# SINTETIZADOR_Y_DDS_SLAVE.net
KiCad netlist of a schematic drawn in Altium Designer
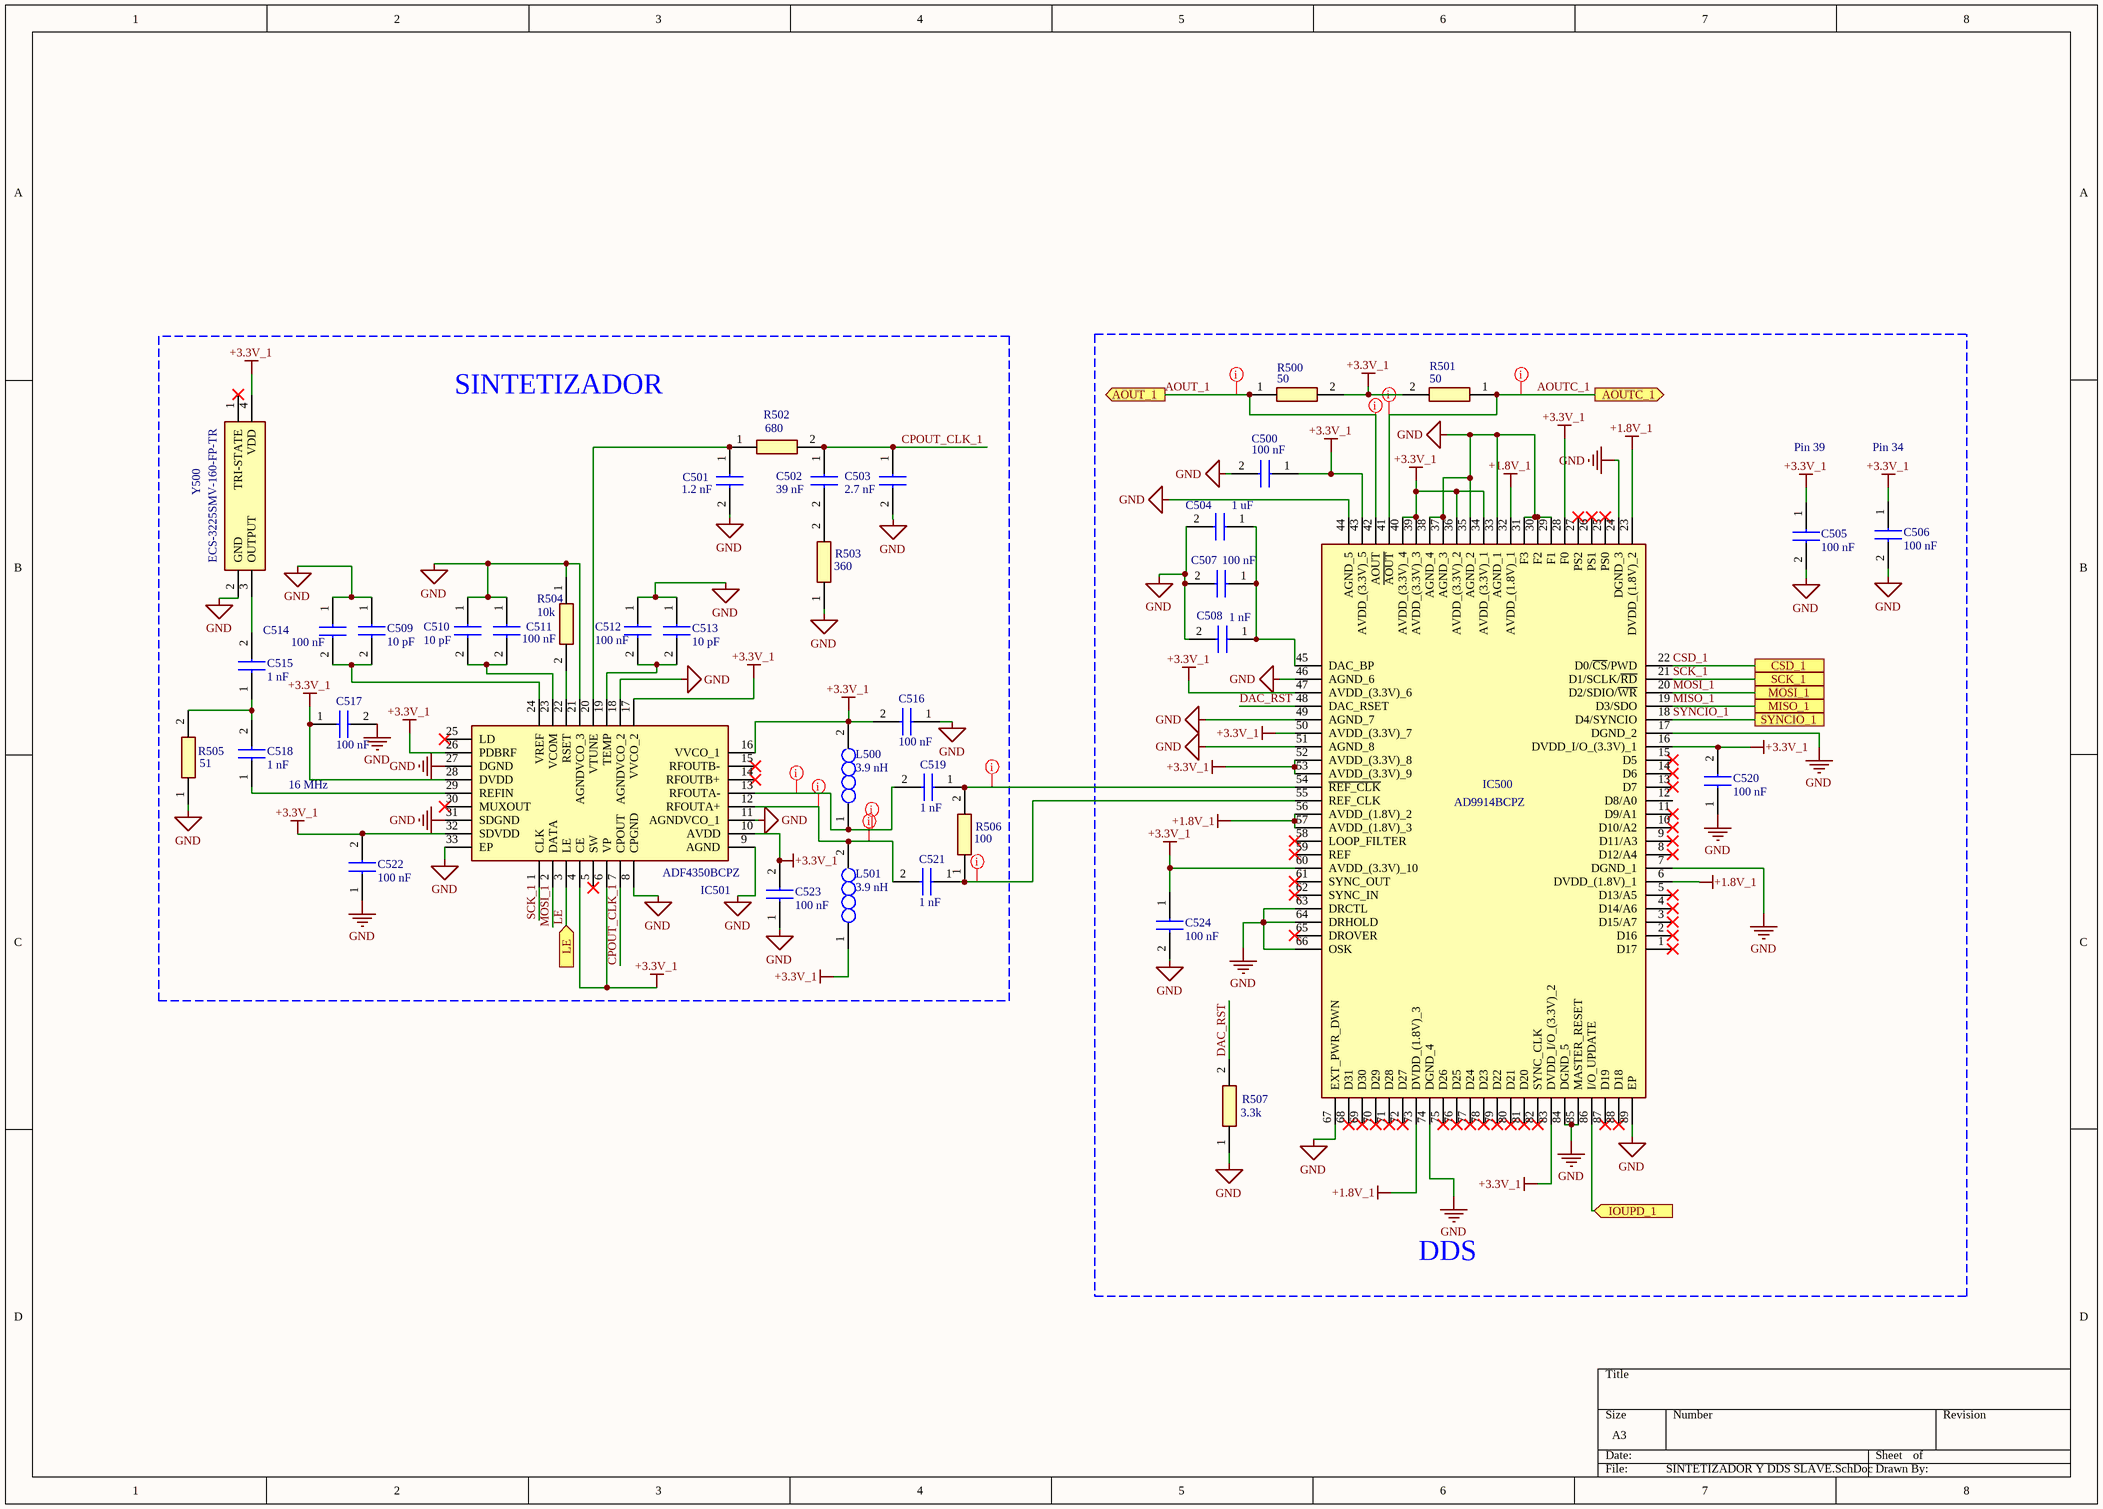
[diagram p0: SINTETIZADOR Y DDS SLAVE.SchDoc]

(export (version "E")
  (design (tool "Eeschema 10.0.6"))
  (components
    (comp (ref "C500")
      (value "100 nF")
      (footprint "SamacSys:C0603")
      (description "Capacitor")
      (fields (field (name "MANUFACTURER_PART_NUMBER") "C0603H470J5GACTU"))
      (libsource (lib "LIBRERIA_GEN_V2.0") (part "C0603H470J5GACTU"))
    )
    (comp (ref "C501")
      (value "1.2 nF")
      (footprint "SamacSys:C0603")
      (description "Capacitor")
      (fields (field (name "MANUFACTURER_PART_NUMBER") "C0603H470J5GACTU"))
      (libsource (lib "LIBRERIA_GEN_V2.0") (part "C0603H470J5GACTU"))
    )
    (comp (ref "C502")
      (value "39 nF")
      (footprint "SamacSys:C0603")
      (description "Capacitor")
      (fields (field (name "MANUFACTURER_PART_NUMBER") "C0603H470J5GACTU"))
      (libsource (lib "LIBRERIA_GEN_V2.0") (part "C0603H470J5GACTU"))
    )
    (comp (ref "C503")
      (value "2.7 nF")
      (footprint "SamacSys:C0603")
      (description "Capacitor")
      (fields (field (name "MANUFACTURER_PART_NUMBER") "C0603H470J5GACTU"))
      (libsource (lib "LIBRERIA_GEN_V2.0") (part "C0603H470J5GACTU"))
    )
    (comp (ref "C504")
      (value "1 uF")
      (footprint "SamacSys:C0603")
      (description "Capacitor")
      (fields (field (name "MANUFACTURER_PART_NUMBER") "C0603H470J5GACTU"))
      (libsource (lib "LIBRERIA_GEN_V2.0") (part "C0603H470J5GACTU"))
    )
    (comp (ref "C505")
      (value "100 nF")
      (footprint "SamacSys:C0603")
      (description "Capacitor")
      (fields (field (name "MANUFACTURER_PART_NUMBER") "C0603H470J5GACTU"))
      (libsource (lib "LIBRERIA_GEN_V2.0") (part "C0603H470J5GACTU"))
    )
    (comp (ref "C506")
      (value "100 nF")
      (footprint "SamacSys:C0603")
      (description "Capacitor")
      (fields (field (name "MANUFACTURER_PART_NUMBER") "C0603H470J5GACTU"))
      (libsource (lib "LIBRERIA_GEN_V2.0") (part "C0603H470J5GACTU"))
    )
    (comp (ref "C507")
      (value "100 nF")
      (footprint "SamacSys:C0603")
      (description "Capacitor")
      (fields (field (name "MANUFACTURER_PART_NUMBER") "C0603H470J5GACTU"))
      (libsource (lib "LIBRERIA_GEN_V2.0") (part "C0603H470J5GACTU"))
    )
    (comp (ref "C508")
      (value "1 nF")
      (footprint "SamacSys:C0603")
      (description "Capacitor")
      (fields (field (name "MANUFACTURER_PART_NUMBER") "C0603H470J5GACTU"))
      (libsource (lib "LIBRERIA_GEN_V2.0") (part "C0603H470J5GACTU"))
    )
    (comp (ref "C509")
      (value "10 pF")
      (footprint "SamacSys:C0603")
      (description "Capacitor")
      (fields (field (name "MANUFACTURER_PART_NUMBER") "C0603H470J5GACTU"))
      (libsource (lib "LIBRERIA_GEN_V2.0") (part "C0603H470J5GACTU"))
    )
    (comp (ref "C510")
      (value "10 pF")
      (footprint "SamacSys:C0603")
      (description "Capacitor")
      (fields (field (name "MANUFACTURER_PART_NUMBER") "C0603H470J5GACTU"))
      (libsource (lib "LIBRERIA_GEN_V2.0") (part "C0603H470J5GACTU"))
    )
    (comp (ref "C511")
      (value "100 nF")
      (footprint "SamacSys:C0603")
      (description "Capacitor")
      (fields (field (name "MANUFACTURER_PART_NUMBER") "C0603H470J5GACTU"))
      (libsource (lib "LIBRERIA_GEN_V2.0") (part "C0603H470J5GACTU"))
    )
    (comp (ref "C512")
      (value "100 nF")
      (footprint "SamacSys:C0603")
      (description "Capacitor")
      (fields (field (name "MANUFACTURER_PART_NUMBER") "C0603H470J5GACTU"))
      (libsource (lib "LIBRERIA_GEN_V2.0") (part "C0603H470J5GACTU"))
    )
    (comp (ref "C513")
      (value "10 pF")
      (footprint "SamacSys:C0603")
      (description "Capacitor")
      (fields (field (name "MANUFACTURER_PART_NUMBER") "C0603H470J5GACTU"))
      (libsource (lib "LIBRERIA_GEN_V2.0") (part "C0603H470J5GACTU"))
    )
    (comp (ref "C514")
      (value "100 nF")
      (footprint "SamacSys:C0603")
      (description "Capacitor")
      (fields (field (name "MANUFACTURER_PART_NUMBER") "C0603H470J5GACTU"))
      (libsource (lib "LIBRERIA_GEN_V2.0") (part "C0603H470J5GACTU"))
    )
    (comp (ref "C515")
      (value "1 nF")
      (footprint "SamacSys:C0603")
      (description "Capacitor")
      (fields (field (name "MANUFACTURER_PART_NUMBER") "C0603H470J5GACTU"))
      (libsource (lib "LIBRERIA_GEN_V2.0") (part "C0603H470J5GACTU"))
    )
    (comp (ref "C516")
      (value "100 nF")
      (footprint "SamacSys:C0603")
      (description "Capacitor")
      (fields (field (name "MANUFACTURER_PART_NUMBER") "C0603H470J5GACTU"))
      (libsource (lib "LIBRERIA_GEN_V2.0") (part "C0603H470J5GACTU"))
    )
    (comp (ref "C517")
      (value "100 nF")
      (footprint "SamacSys:C0603")
      (description "Capacitor")
      (fields (field (name "MANUFACTURER_PART_NUMBER") "C0603H470J5GACTU"))
      (libsource (lib "LIBRERIA_GEN_V2.0") (part "C0603H470J5GACTU"))
    )
    (comp (ref "C518")
      (value "1 nF")
      (footprint "SamacSys:C0603")
      (description "Capacitor")
      (fields (field (name "MANUFACTURER_PART_NUMBER") "C0603H470J5GACTU"))
      (libsource (lib "LIBRERIA_GEN_V2.0") (part "C0603H470J5GACTU"))
    )
    (comp (ref "C519")
      (value "1 nF")
      (footprint "SamacSys:C0603")
      (description "Capacitor")
      (fields (field (name "MANUFACTURER_PART_NUMBER") "C0603H470J5GACTU"))
      (libsource (lib "LIBRERIA_GEN_V2.0") (part "C0603H470J5GACTU"))
    )
    (comp (ref "C520")
      (value "100 nF")
      (footprint "SamacSys:C0603")
      (description "Capacitor")
      (fields (field (name "MANUFACTURER_PART_NUMBER") "C0603H470J5GACTU"))
      (libsource (lib "LIBRERIA_GEN_V2.0") (part "C0603H470J5GACTU"))
    )
    (comp (ref "C521")
      (value "1 nF")
      (footprint "SamacSys:C0603")
      (description "Capacitor")
      (fields (field (name "MANUFACTURER_PART_NUMBER") "C0603H470J5GACTU"))
      (libsource (lib "LIBRERIA_GEN_V2.0") (part "C0603H470J5GACTU"))
    )
    (comp (ref "C522")
      (value "100 nF")
      (footprint "SamacSys:C0603")
      (description "Capacitor")
      (fields (field (name "MANUFACTURER_PART_NUMBER") "C0603H470J5GACTU"))
      (libsource (lib "LIBRERIA_GEN_V2.0") (part "C0603H470J5GACTU"))
    )
    (comp (ref "C523")
      (value "100 nF")
      (footprint "SamacSys:C0603")
      (description "Capacitor")
      (fields (field (name "MANUFACTURER_PART_NUMBER") "C0603H470J5GACTU"))
      (libsource (lib "LIBRERIA_GEN_V2.0") (part "C0603H470J5GACTU"))
    )
    (comp (ref "C524")
      (value "100 nF")
      (footprint "SamacSys:C0603")
      (description "Capacitor")
      (fields (field (name "MANUFACTURER_PART_NUMBER") "C0603H470J5GACTU"))
      (libsource (lib "LIBRERIA_GEN_V2.0") (part "C0603H470J5GACTU"))
    )
    (comp (ref "IC500")
      (value "AD9914BCPZ")
      (footprint "SamacSys:QFN50P1200X1200X90-89N-D")
      (description "Integrated Circuit")
      (fields (field (name "MOUSER PART NUMBER") "584-AD9914BCPZ"))
      (libsource (lib "LIBRERIA_GEN_V2.0") (part "AD9914BCPZ"))
    )
    (comp (ref "IC501")
      (value "ADF4350BCPZ")
      (footprint "SamacSys:QFN50P500X500X100-33N")
      (description "Integrated Circuit")
      (fields (field (name "MOUSER PART NUMBER") "584-ADF4350BCPZ"))
      (libsource (lib "LIBRERIA_GEN_V2.0") (part "ADF4350BCPZ"))
    )
    (comp (ref "L500")
      (value "3.9 nH")
      (footprint "SamacSys:INDC1608X95N")
      (description "Inductor")
      (fields
        (field (name "MANUFACTURER_PART_NUMBER") "AIML-0603-100K-T")
        (field (name "MOUSER PART NUMBER") "815-AIML-0603-100KT")
      )
      (libsource (lib "*") (part "AIML-0603-100K-T"))
    )
    (comp (ref "L501")
      (value "3.9 nH")
      (footprint "SamacSys:INDC1608X95N")
      (description "Inductor")
      (fields
        (field (name "MANUFACTURER_PART_NUMBER") "AIML-0603-100K-T")
        (field (name "MOUSER PART NUMBER") "815-AIML-0603-100KT")
      )
      (libsource (lib "*") (part "AIML-0603-100K-T"))
    )
    (comp (ref "R500")
      (value "50")
      (footprint "SamacSys:RESC1608X55N")
      (description "Resistor")
      (fields
        (field (name "MANUFACTURER_PART_NUMBER") "CR0603-FX-1431ELF")
        (field (name "MOUSER PART NUMBER") "652-CR0603FX-1431ELF")
      )
      (libsource (lib "LIBRERIA_GEN_V2.0") (part "CR0603-FX-1431ELF"))
    )
    (comp (ref "R501")
      (value "50")
      (footprint "SamacSys:RESC1608X55N")
      (description "Resistor")
      (fields
        (field (name "MANUFACTURER_PART_NUMBER") "CR0603-FX-1431ELF")
        (field (name "MOUSER PART NUMBER") "652-CR0603FX-1431ELF")
      )
      (libsource (lib "") (part "CR0603-FX-1431ELF_2"))
    )
    (comp (ref "R502")
      (value "680")
      (footprint "SamacSys:RESC1608X55N")
      (description "Resistor")
      (fields
        (field (name "MANUFACTURER_PART_NUMBER") "CR0603-FX-1431ELF")
        (field (name "MOUSER PART NUMBER") "652-CR0603FX-1431ELF")
      )
      (libsource (lib "LIBRERIA_GEN_V2.0") (part "CR0603-FX-1431ELF"))
    )
    (comp (ref "R503")
      (value "360")
      (footprint "SamacSys:RESC1608X55N")
      (description "Resistor")
      (fields
        (field (name "MANUFACTURER_PART_NUMBER") "CR0603-FX-1431ELF")
        (field (name "MOUSER PART NUMBER") "652-CR0603FX-1431ELF")
      )
      (libsource (lib "") (part "CR0603-FX-1431ELF_3"))
    )
    (comp (ref "R504")
      (value "10k")
      (footprint "SamacSys:RESC1608X55N")
      (description "Resistor")
      (fields
        (field (name "MANUFACTURER_PART_NUMBER") "CR0603-FX-1431ELF")
        (field (name "MOUSER PART NUMBER") "652-CR0603FX-1431ELF")
      )
      (libsource (lib "") (part "CR0603-FX-1431ELF_1"))
    )
    (comp (ref "R505")
      (value "51")
      (footprint "SamacSys:RESC1608X55N")
      (description "Resistor")
      (fields
        (field (name "MANUFACTURER_PART_NUMBER") "CR0603-FX-1431ELF")
        (field (name "MOUSER PART NUMBER") "652-CR0603FX-1431ELF")
      )
      (libsource (lib "") (part "CR0603-FX-1431ELF_3"))
    )
    (comp (ref "R506")
      (value "100")
      (footprint "SamacSys:RESC1608X55N")
      (description "Resistor")
      (fields
        (field (name "MANUFACTURER_PART_NUMBER") "CR0603-FX-1431ELF")
        (field (name "MOUSER PART NUMBER") "652-CR0603FX-1431ELF")
      )
      (libsource (lib "") (part "CR0603-FX-1431ELF_3"))
    )
    (comp (ref "R507")
      (value "3.3k")
      (footprint "SamacSys:RESC1608X55N")
      (description "Resistor")
      (fields
        (field (name "MANUFACTURER_PART_NUMBER") "CR0603-FX-1431ELF")
        (field (name "MOUSER PART NUMBER") "652-CR0603FX-1431ELF")
      )
      (libsource (lib "") (part "CR0603-FX-1431ELF_3"))
    )
    (comp (ref "Y500")
      (value "ECS-3225SMV-160-FP-TR")
      (footprint "SamacSys:ECS3225SMV160FPTR")
      (description "Crystal or Oscillator")
      (fields (field (name "MOUSER PART NUMBER") "520-3225SMV-160-FPT"))
      (libsource (lib "LIBRERIA_GEN_V2.0") (part "ECS-3225SMV-160-FP-TR"))
    )
  )
  (nets
    (net (code "1") (name "+1.8V_1") (class "Default")
      (node (ref "IC500") (pin "23") (pinfunction "DVDD_(1.8V)_2_23") (pintype "passive"))
      (node (ref "IC500") (pin "32") (pinfunction "AVDD_(1.8V)_1_32") (pintype "passive"))
      (node (ref "IC500") (pin "56") (pinfunction "AVDD_(1.8V)_2_56") (pintype "passive"))
      (node (ref "IC500") (pin "57") (pinfunction "AVDD_(1.8V)_3_57") (pintype "passive"))
      (node (ref "IC500") (pin "6") (pinfunction "DVDD_(1.8V)_1_6") (pintype "passive"))
      (node (ref "IC500") (pin "73") (pinfunction "DVDD_(1.8V)_3_73") (pintype "passive"))
    )
    (net (code "2") (name "+3.3V_1") (class "Default")
      (node (ref "C500") (pin "1") (pinfunction "1_1") (pintype "passive"))
      (node (ref "C505") (pin "1") (pinfunction "1_1") (pintype "passive"))
      (node (ref "C506") (pin "1") (pinfunction "1_1") (pintype "passive"))
      (node (ref "C516") (pin "2") (pinfunction "2_2") (pintype "passive"))
      (node (ref "C517") (pin "1") (pinfunction "1_1") (pintype "passive"))
      (node (ref "C520") (pin "2") (pinfunction "2_2") (pintype "passive"))
      (node (ref "C522") (pin "2") (pinfunction "2_2") (pintype "passive"))
      (node (ref "C523") (pin "2") (pinfunction "2_2") (pintype "passive"))
      (node (ref "C524") (pin "1") (pinfunction "1_1") (pintype "passive"))
      (node (ref "IC500") (pin "16") (pinfunction "DVDD_I/O_(3.3V)_1_16") (pintype "passive"))
      (node (ref "IC500") (pin "28") (pinfunction "F0_28") (pintype "passive"))
      (node (ref "IC500") (pin "34") (pinfunction "AVDD_(3.3V)_1_34") (pintype "passive"))
      (node (ref "IC500") (pin "36") (pinfunction "AVDD_(3.3V)_2_36") (pintype "passive"))
      (node (ref "IC500") (pin "39") (pinfunction "AVDD_(3.3V)_3_39") (pintype "passive"))
      (node (ref "IC500") (pin "40") (pinfunction "AVDD_(3.3V)_4_40") (pintype "passive"))
      (node (ref "IC500") (pin "43") (pinfunction "AVDD_(3.3V)_5_43") (pintype "passive"))
      (node (ref "IC500") (pin "47") (pinfunction "AVDD_(3.3V)_6_47") (pintype "passive"))
      (node (ref "IC500") (pin "50") (pinfunction "AVDD_(3.3V)_7_50") (pintype "passive"))
      (node (ref "IC500") (pin "52") (pinfunction "AVDD_(3.3V)_8_52") (pintype "passive"))
      (node (ref "IC500") (pin "53") (pinfunction "AVDD_(3.3V)_9_53") (pintype "passive"))
      (node (ref "IC500") (pin "60") (pinfunction "AVDD_(3.3V)_10_60") (pintype "passive"))
      (node (ref "IC500") (pin "83") (pinfunction "DVDD_I/O_(3.3V)_2_83") (pintype "passive"))
      (node (ref "IC501") (pin "10") (pinfunction "AVDD_10") (pintype "passive"))
      (node (ref "IC501") (pin "16") (pinfunction "VVCO_1_16") (pintype "passive"))
      (node (ref "IC501") (pin "17") (pinfunction "VVCO_2_17") (pintype "passive"))
      (node (ref "IC501") (pin "26") (pinfunction "PDBRF_26") (pintype "passive"))
      (node (ref "IC501") (pin "28") (pinfunction "DVDD_28") (pintype "passive"))
      (node (ref "IC501") (pin "32") (pinfunction "SDVDD_32") (pintype "passive"))
      (node (ref "IC501") (pin "4") (pinfunction "CE_4") (pintype "passive"))
      (node (ref "IC501") (pin "6") (pinfunction "VP_6") (pintype "passive"))
      (node (ref "L500") (pin "2") (pinfunction "2_2") (pintype "passive"))
      (node (ref "L501") (pin "1") (pinfunction "1_1") (pintype "passive"))
      (node (ref "R500") (pin "2") (pinfunction "2_2") (pintype "passive"))
      (node (ref "R501") (pin "2") (pinfunction "2_2") (pintype "passive"))
      (node (ref "Y500") (pin "4") (pinfunction "VDD_4") (pintype "passive"))
    )
    (net (code "3") (name "/AOUTC_1") (class "Default")
      (node (ref "IC500") (pin "41") (pinfunction "~{AOUT}_41") (pintype "passive"))
      (node (ref "R501") (pin "1") (pinfunction "1_1") (pintype "passive"))
    )
    (net (code "4") (name "/AOUT_1") (class "Default")
      (node (ref "IC500") (pin "42") (pinfunction "AOUT_42") (pintype "passive"))
      (node (ref "R500") (pin "1") (pinfunction "1_1") (pintype "passive"))
    )
    (net (code "5") (name "/CPOUT_CLK_1") (class "Default")
      (node (ref "C502") (pin "1") (pinfunction "1_1") (pintype "passive"))
      (node (ref "C503") (pin "1") (pinfunction "1_1") (pintype "passive"))
      (node (ref "IC501") (pin "7") (pinfunction "CPOUT_7") (pintype "passive"))
      (node (ref "R502") (pin "2") (pinfunction "2_2") (pintype "passive"))
    )
    (net (code "6") (name "/CSD_1") (class "Default")
      (node (ref "IC500") (pin "22") (pinfunction "D0/~{CS}/PWD_22") (pintype "passive"))
    )
    (net (code "7") (name "/DAC_RST") (class "Default")
      (node (ref "IC500") (pin "48") (pinfunction "DAC_RSET_48") (pintype "passive"))
      (node (ref "R507") (pin "2") (pinfunction "2_2") (pintype "passive"))
    )
    (net (code "8") (name "/IOUPD_1") (class "Default")
      (node (ref "IC500") (pin "86") (pinfunction "I/O_UPDATE_86") (pintype "passive"))
    )
    (net (code "9") (name "/LE") (class "Default")
      (node (ref "IC501") (pin "3") (pinfunction "LE_3") (pintype "passive"))
    )
    (net (code "10") (name "/MISO_1") (class "Default")
      (node (ref "IC500") (pin "19") (pinfunction "D3/SDO_19") (pintype "passive"))
    )
    (net (code "11") (name "/MOSI_1") (class "Default")
      (node (ref "IC500") (pin "20") (pinfunction "D2/SDIO/~{WR}_20") (pintype "passive"))
      (node (ref "IC501") (pin "2") (pinfunction "DATA_2") (pintype "passive"))
    )
    (net (code "12") (name "/SCK_1") (class "Default")
      (node (ref "IC500") (pin "21") (pinfunction "D1/SCLK/~{RD}_21") (pintype "passive"))
      (node (ref "IC501") (pin "1") (pinfunction "CLK_1") (pintype "passive"))
    )
    (net (code "13") (name "/SYNCIO_1") (class "Default")
      (node (ref "IC500") (pin "18") (pinfunction "D4/SYNCIO_18") (pintype "passive"))
    )
    (net (code "14") (name "GND") (class "Default")
      (node (ref "C500") (pin "2") (pinfunction "2_2") (pintype "passive"))
      (node (ref "C501") (pin "2") (pinfunction "2_2") (pintype "passive"))
      (node (ref "C503") (pin "2") (pinfunction "2_2") (pintype "passive"))
      (node (ref "C504") (pin "2") (pinfunction "2_2") (pintype "passive"))
      (node (ref "C505") (pin "2") (pinfunction "2_2") (pintype "passive"))
      (node (ref "C506") (pin "2") (pinfunction "2_2") (pintype "passive"))
      (node (ref "C507") (pin "2") (pinfunction "2_2") (pintype "passive"))
      (node (ref "C508") (pin "2") (pinfunction "2_2") (pintype "passive"))
      (node (ref "C509") (pin "1") (pinfunction "1_1") (pintype "passive"))
      (node (ref "C510") (pin "1") (pinfunction "1_1") (pintype "passive"))
      (node (ref "C511") (pin "1") (pinfunction "1_1") (pintype "passive"))
      (node (ref "C512") (pin "1") (pinfunction "1_1") (pintype "passive"))
      (node (ref "C513") (pin "1") (pinfunction "1_1") (pintype "passive"))
      (node (ref "C514") (pin "1") (pinfunction "1_1") (pintype "passive"))
      (node (ref "C516") (pin "1") (pinfunction "1_1") (pintype "passive"))
      (node (ref "C517") (pin "2") (pinfunction "2_2") (pintype "passive"))
      (node (ref "C520") (pin "1") (pinfunction "1_1") (pintype "passive"))
      (node (ref "C522") (pin "1") (pinfunction "1_1") (pintype "passive"))
      (node (ref "C523") (pin "1") (pinfunction "1_1") (pintype "passive"))
      (node (ref "C524") (pin "2") (pinfunction "2_2") (pintype "passive"))
      (node (ref "IC500") (pin "17") (pinfunction "DGND_2_17") (pintype "passive"))
      (node (ref "IC500") (pin "24") (pinfunction "DGND_3_24") (pintype "passive"))
      (node (ref "IC500") (pin "29") (pinfunction "F1_29") (pintype "passive"))
      (node (ref "IC500") (pin "30") (pinfunction "F2_30") (pintype "passive"))
      (node (ref "IC500") (pin "31") (pinfunction "F3_31") (pintype "passive"))
      (node (ref "IC500") (pin "33") (pinfunction "AGND_1_33") (pintype "passive"))
      (node (ref "IC500") (pin "35") (pinfunction "AGND_2_35") (pintype "passive"))
      (node (ref "IC500") (pin "37") (pinfunction "AGND_3_37") (pintype "passive"))
      (node (ref "IC500") (pin "38") (pinfunction "AGND_4_38") (pintype "passive"))
      (node (ref "IC500") (pin "44") (pinfunction "AGND_5_44") (pintype "passive"))
      (node (ref "IC500") (pin "46") (pinfunction "AGND_6_46") (pintype "passive"))
      (node (ref "IC500") (pin "49") (pinfunction "AGND_7_49") (pintype "passive"))
      (node (ref "IC500") (pin "51") (pinfunction "AGND_8_51") (pintype "passive"))
      (node (ref "IC500") (pin "63") (pinfunction "DRCTL_63") (pintype "passive"))
      (node (ref "IC500") (pin "64") (pinfunction "DRHOLD_64") (pintype "passive"))
      (node (ref "IC500") (pin "66") (pinfunction "OSK_66") (pintype "passive"))
      (node (ref "IC500") (pin "67") (pinfunction "EXT_PWR_DWN_67") (pintype "passive"))
      (node (ref "IC500") (pin "7") (pinfunction "DGND_1_7") (pintype "passive"))
      (node (ref "IC500") (pin "74") (pinfunction "DGND_4_74") (pintype "passive"))
      (node (ref "IC500") (pin "84") (pinfunction "DGND_5_84") (pintype "passive"))
      (node (ref "IC500") (pin "85") (pinfunction "MASTER_RESET_85") (pintype "passive"))
      (node (ref "IC500") (pin "89") (pinfunction "EP_89") (pintype "passive"))
      (node (ref "IC501") (pin "11") (pinfunction "AGNDVCO_1_11") (pintype "passive"))
      (node (ref "IC501") (pin "18") (pinfunction "AGNDVCO_2_18") (pintype "passive"))
      (node (ref "IC501") (pin "21") (pinfunction "AGNDVCO_3_21") (pintype "passive"))
      (node (ref "IC501") (pin "27") (pinfunction "DGND_27") (pintype "passive"))
      (node (ref "IC501") (pin "31") (pinfunction "SDGND_31") (pintype "passive"))
      (node (ref "IC501") (pin "33") (pinfunction "EP_33") (pintype "passive"))
      (node (ref "IC501") (pin "8") (pinfunction "CPGND_8") (pintype "passive"))
      (node (ref "IC501") (pin "9") (pinfunction "AGND_9") (pintype "passive"))
      (node (ref "R503") (pin "1") (pinfunction "1_1") (pintype "passive"))
      (node (ref "R504") (pin "1") (pinfunction "1_1") (pintype "passive"))
      (node (ref "R505") (pin "1") (pinfunction "1_1") (pintype "passive"))
      (node (ref "R507") (pin "1") (pinfunction "1_1") (pintype "passive"))
      (node (ref "Y500") (pin "2") (pinfunction "GND_2") (pintype "passive"))
    )
    (net (code "15") (name "Net-(C502-Pad2)") (class "Default")
      (node (ref "C502") (pin "2") (pinfunction "2_2") (pintype "passive"))
      (node (ref "R503") (pin "2") (pinfunction "2_2") (pintype "passive"))
    )
    (net (code "16") (name "Net-(C515-Pad1)") (class "Default")
      (node (ref "C515") (pin "1") (pinfunction "1_1") (pintype "passive"))
      (node (ref "C518") (pin "2") (pinfunction "2_2") (pintype "passive"))
      (node (ref "R505") (pin "2") (pinfunction "2_2") (pintype "passive"))
    )
    (net (code "17") (name "Net-(IC500-DAC_BP)") (class "Default")
      (node (ref "C504") (pin "1") (pinfunction "1_1") (pintype "passive"))
      (node (ref "C507") (pin "1") (pinfunction "1_1") (pintype "passive"))
      (node (ref "C508") (pin "1") (pinfunction "1_1") (pintype "passive"))
      (node (ref "IC500") (pin "45") (pinfunction "DAC_BP_45") (pintype "passive"))
    )
    (net (code "18") (name "Net-(IC500-REF_CLK)") (class "Default")
      (node (ref "C521") (pin "1") (pinfunction "1_1") (pintype "passive"))
      (node (ref "IC500") (pin "55") (pinfunction "REF_CLK_55") (pintype "passive"))
      (node (ref "R506") (pin "1") (pinfunction "1_1") (pintype "passive"))
    )
    (net (code "19") (name "Net-(IC500-~{REF_CLK})") (class "Default")
      (node (ref "C519") (pin "1") (pinfunction "1_1") (pintype "passive"))
      (node (ref "IC500") (pin "54") (pinfunction "~{REF_CLK}_54") (pintype "passive"))
      (node (ref "R506") (pin "2") (pinfunction "2_2") (pintype "passive"))
    )
    (net (code "20") (name "Net-(IC501-REFIN)") (class "Default")
      (node (ref "C518") (pin "1") (pinfunction "1_1") (pintype "passive"))
      (node (ref "IC501") (pin "29") (pinfunction "REFIN_29") (pintype "passive"))
    )
    (net (code "21") (name "Net-(IC501-RFOUTA+)") (class "Default")
      (node (ref "C521") (pin "2") (pinfunction "2_2") (pintype "passive"))
      (node (ref "IC501") (pin "12") (pinfunction "RFOUTA+_12") (pintype "passive"))
      (node (ref "L501") (pin "2") (pinfunction "2_2") (pintype "passive"))
    )
    (net (code "22") (name "Net-(IC501-RFOUTA-)") (class "Default")
      (node (ref "C519") (pin "2") (pinfunction "2_2") (pintype "passive"))
      (node (ref "IC501") (pin "13") (pinfunction "RFOUTA-_13") (pintype "passive"))
      (node (ref "L500") (pin "1") (pinfunction "1_1") (pintype "passive"))
    )
    (net (code "23") (name "Net-(IC501-RSET)") (class "Default")
      (node (ref "IC501") (pin "22") (pinfunction "RSET_22") (pintype "passive"))
      (node (ref "R504") (pin "2") (pinfunction "2_2") (pintype "passive"))
    )
    (net (code "24") (name "Net-(IC501-TEMP)") (class "Default")
      (node (ref "C512") (pin "2") (pinfunction "2_2") (pintype "passive"))
      (node (ref "C513") (pin "2") (pinfunction "2_2") (pintype "passive"))
      (node (ref "IC501") (pin "19") (pinfunction "TEMP_19") (pintype "passive"))
    )
    (net (code "25") (name "Net-(IC501-VCOM)") (class "Default")
      (node (ref "C510") (pin "2") (pinfunction "2_2") (pintype "passive"))
      (node (ref "C511") (pin "2") (pinfunction "2_2") (pintype "passive"))
      (node (ref "IC501") (pin "23") (pinfunction "VCOM_23") (pintype "passive"))
    )
    (net (code "26") (name "Net-(IC501-VREF)") (class "Default")
      (node (ref "C509") (pin "2") (pinfunction "2_2") (pintype "passive"))
      (node (ref "C514") (pin "2") (pinfunction "2_2") (pintype "passive"))
      (node (ref "IC501") (pin "24") (pinfunction "VREF_24") (pintype "passive"))
    )
    (net (code "27") (name "Net-(IC501-VTUNE)") (class "Default")
      (node (ref "C501") (pin "1") (pinfunction "1_1") (pintype "passive"))
      (node (ref "IC501") (pin "20") (pinfunction "VTUNE_20") (pintype "passive"))
      (node (ref "R502") (pin "1") (pinfunction "1_1") (pintype "passive"))
    )
    (net (code "28") (name "Net-(Y500-OUTPUT)") (class "Default")
      (node (ref "C515") (pin "2") (pinfunction "2_2") (pintype "passive"))
      (node (ref "Y500") (pin "3") (pinfunction "OUTPUT_3") (pintype "passive"))
    )
    (net (code "29") (name "unconnected-(IC500-D5-Pad15)") (class "Default")
      (node (ref "IC500") (pin "15") (pinfunction "D5_15") (pintype "passive+no_connect"))
    )
    (net (code "30") (name "unconnected-(IC500-D6-Pad14)") (class "Default")
      (node (ref "IC500") (pin "14") (pinfunction "D6_14") (pintype "passive+no_connect"))
    )
    (net (code "31") (name "unconnected-(IC500-D7-Pad13)") (class "Default")
      (node (ref "IC500") (pin "13") (pinfunction "D7_13") (pintype "passive+no_connect"))
    )
    (net (code "32") (name "unconnected-(IC500-D8{slash}A0-Pad12)") (class "Default")
      (node (ref "IC500") (pin "12") (pinfunction "D8/A0_12") (pintype "passive"))
    )
    (net (code "33") (name "unconnected-(IC500-D9{slash}A1-Pad11)") (class "Default")
      (node (ref "IC500") (pin "11") (pinfunction "D9/A1_11") (pintype "passive+no_connect"))
    )
    (net (code "34") (name "unconnected-(IC500-D10{slash}A2-Pad10)") (class "Default")
      (node (ref "IC500") (pin "10") (pinfunction "D10/A2_10") (pintype "passive+no_connect"))
    )
    (net (code "35") (name "unconnected-(IC500-D11{slash}A3-Pad9)") (class "Default")
      (node (ref "IC500") (pin "9") (pinfunction "D11/A3_9") (pintype "passive+no_connect"))
    )
    (net (code "36") (name "unconnected-(IC500-D12{slash}A4-Pad8)") (class "Default")
      (node (ref "IC500") (pin "8") (pinfunction "D12/A4_8") (pintype "passive+no_connect"))
    )
    (net (code "37") (name "unconnected-(IC500-D13{slash}A5-Pad5)") (class "Default")
      (node (ref "IC500") (pin "5") (pinfunction "D13/A5_5") (pintype "passive+no_connect"))
    )
    (net (code "38") (name "unconnected-(IC500-D14{slash}A6-Pad4)") (class "Default")
      (node (ref "IC500") (pin "4") (pinfunction "D14/A6_4") (pintype "passive+no_connect"))
    )
    (net (code "39") (name "unconnected-(IC500-D15{slash}A7-Pad3)") (class "Default")
      (node (ref "IC500") (pin "3") (pinfunction "D15/A7_3") (pintype "passive+no_connect"))
    )
    (net (code "40") (name "unconnected-(IC500-D16-Pad2)") (class "Default")
      (node (ref "IC500") (pin "2") (pinfunction "D16_2") (pintype "passive+no_connect"))
    )
    (net (code "41") (name "unconnected-(IC500-D17-Pad1)") (class "Default")
      (node (ref "IC500") (pin "1") (pinfunction "D17_1") (pintype "passive+no_connect"))
    )
    (net (code "42") (name "unconnected-(IC500-D18-Pad88)") (class "Default")
      (node (ref "IC500") (pin "88") (pinfunction "D18_88") (pintype "passive+no_connect"))
    )
    (net (code "43") (name "unconnected-(IC500-D19-Pad87)") (class "Default")
      (node (ref "IC500") (pin "87") (pinfunction "D19_87") (pintype "passive+no_connect"))
    )
    (net (code "44") (name "unconnected-(IC500-D20-Pad81)") (class "Default")
      (node (ref "IC500") (pin "81") (pinfunction "D20_81") (pintype "passive+no_connect"))
    )
    (net (code "45") (name "unconnected-(IC500-D21-Pad80)") (class "Default")
      (node (ref "IC500") (pin "80") (pinfunction "D21_80") (pintype "passive+no_connect"))
    )
    (net (code "46") (name "unconnected-(IC500-D22-Pad79)") (class "Default")
      (node (ref "IC500") (pin "79") (pinfunction "D22_79") (pintype "passive+no_connect"))
    )
    (net (code "47") (name "unconnected-(IC500-D23-Pad78)") (class "Default")
      (node (ref "IC500") (pin "78") (pinfunction "D23_78") (pintype "passive+no_connect"))
    )
    (net (code "48") (name "unconnected-(IC500-D24-Pad77)") (class "Default")
      (node (ref "IC500") (pin "77") (pinfunction "D24_77") (pintype "passive+no_connect"))
    )
    (net (code "49") (name "unconnected-(IC500-D25-Pad76)") (class "Default")
      (node (ref "IC500") (pin "76") (pinfunction "D25_76") (pintype "passive+no_connect"))
    )
    (net (code "50") (name "unconnected-(IC500-D26-Pad75)") (class "Default")
      (node (ref "IC500") (pin "75") (pinfunction "D26_75") (pintype "passive+no_connect"))
    )
    (net (code "51") (name "unconnected-(IC500-D27-Pad72)") (class "Default")
      (node (ref "IC500") (pin "72") (pinfunction "D27_72") (pintype "passive+no_connect"))
    )
    (net (code "52") (name "unconnected-(IC500-D28-Pad71)") (class "Default")
      (node (ref "IC500") (pin "71") (pinfunction "D28_71") (pintype "passive+no_connect"))
    )
    (net (code "53") (name "unconnected-(IC500-D29-Pad70)") (class "Default")
      (node (ref "IC500") (pin "70") (pinfunction "D29_70") (pintype "passive+no_connect"))
    )
    (net (code "54") (name "unconnected-(IC500-D30-Pad69)") (class "Default")
      (node (ref "IC500") (pin "69") (pinfunction "D30_69") (pintype "passive+no_connect"))
    )
    (net (code "55") (name "unconnected-(IC500-D31-Pad68)") (class "Default")
      (node (ref "IC500") (pin "68") (pinfunction "D31_68") (pintype "passive+no_connect"))
    )
    (net (code "56") (name "unconnected-(IC500-DROVER-Pad65)") (class "Default")
      (node (ref "IC500") (pin "65") (pinfunction "DROVER_65") (pintype "passive+no_connect"))
    )
    (net (code "57") (name "unconnected-(IC500-LOOP_FILTER-Pad58)") (class "Default")
      (node (ref "IC500") (pin "58") (pinfunction "LOOP_FILTER_58") (pintype "passive+no_connect"))
    )
    (net (code "58") (name "unconnected-(IC500-PS0-Pad25)") (class "Default")
      (node (ref "IC500") (pin "25") (pinfunction "PS0_25") (pintype "passive+no_connect"))
    )
    (net (code "59") (name "unconnected-(IC500-PS1-Pad26)") (class "Default")
      (node (ref "IC500") (pin "26") (pinfunction "PS1_26") (pintype "passive+no_connect"))
    )
    (net (code "60") (name "unconnected-(IC500-PS2-Pad27)") (class "Default")
      (node (ref "IC500") (pin "27") (pinfunction "PS2_27") (pintype "passive+no_connect"))
    )
    (net (code "61") (name "unconnected-(IC500-REF-Pad59)") (class "Default")
      (node (ref "IC500") (pin "59") (pinfunction "REF_59") (pintype "passive+no_connect"))
    )
    (net (code "62") (name "unconnected-(IC500-SYNC_CLK-Pad82)") (class "Default")
      (node (ref "IC500") (pin "82") (pinfunction "SYNC_CLK_82") (pintype "passive+no_connect"))
    )
    (net (code "63") (name "unconnected-(IC500-SYNC_IN-Pad62)") (class "Default")
      (node (ref "IC500") (pin "62") (pinfunction "SYNC_IN_62") (pintype "passive+no_connect"))
    )
    (net (code "64") (name "unconnected-(IC500-SYNC_OUT-Pad61)") (class "Default")
      (node (ref "IC500") (pin "61") (pinfunction "SYNC_OUT_61") (pintype "passive+no_connect"))
    )
    (net (code "65") (name "unconnected-(IC501-LD-Pad25)") (class "Default")
      (node (ref "IC501") (pin "25") (pinfunction "LD_25") (pintype "passive+no_connect"))
    )
    (net (code "66") (name "unconnected-(IC501-MUXOUT-Pad30)") (class "Default")
      (node (ref "IC501") (pin "30") (pinfunction "MUXOUT_30") (pintype "passive+no_connect"))
    )
    (net (code "67") (name "unconnected-(IC501-RFOUTB+-Pad14)") (class "Default")
      (node (ref "IC501") (pin "14") (pinfunction "RFOUTB+_14") (pintype "passive+no_connect"))
    )
    (net (code "68") (name "unconnected-(IC501-RFOUTB--Pad15)") (class "Default")
      (node (ref "IC501") (pin "15") (pinfunction "RFOUTB-_15") (pintype "passive+no_connect"))
    )
    (net (code "69") (name "unconnected-(IC501-SW-Pad5)") (class "Default")
      (node (ref "IC501") (pin "5") (pinfunction "SW_5") (pintype "passive+no_connect"))
    )
    (net (code "70") (name "unconnected-(Y500-TRI-STATE-Pad1)") (class "Default")
      (node (ref "Y500") (pin "1") (pinfunction "TRI-STATE_1") (pintype "passive+no_connect"))
    )
  )
)
